# SH3-USB_AND_UART.net
KiCad netlist of a schematic drawn in Altium Designer
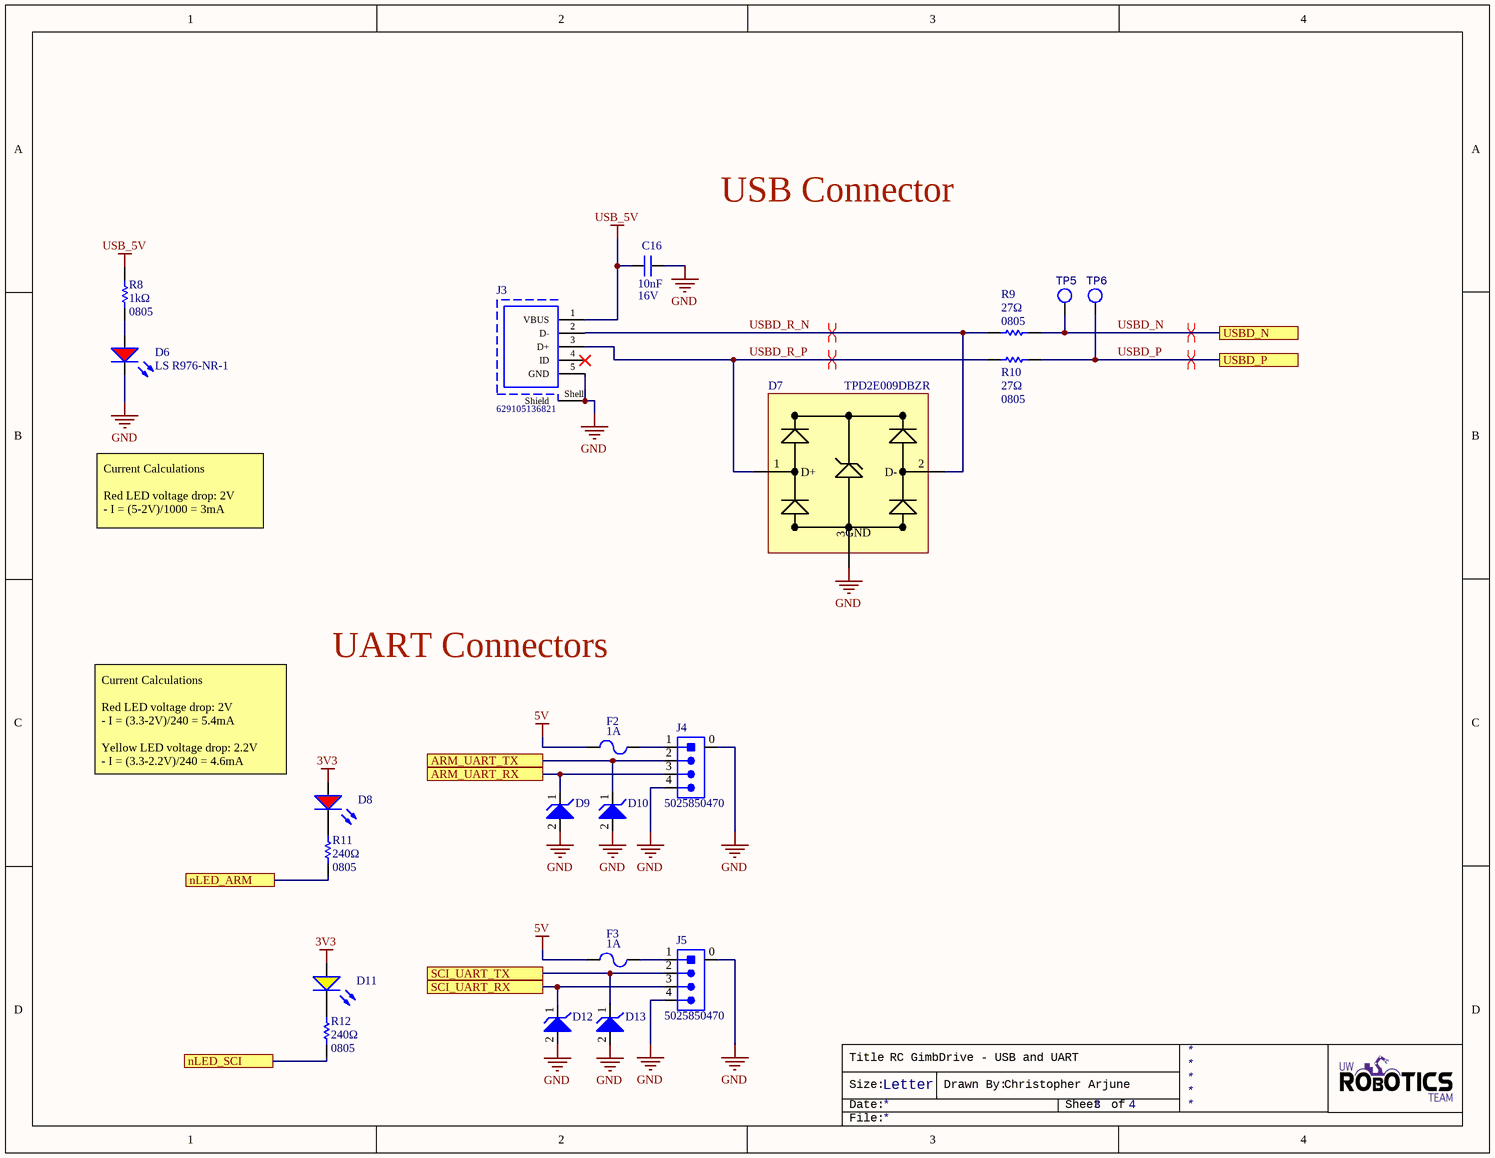
[diagram p0: SH3-USB AND UART.SchDoc]

(export (version "E")
  (design (tool "Eeschema 10.0.6"))
  (components
    (comp (ref "C16")
      (value "~")
      (footprint "CAPC2012X140N")
      (description "CAP CER 10000PF 16V X7R 0805")
      (fields
        (field (name "TOLERANCE") "10%")
        (field (name "CAPACITANCE") "10nF")
        (field (name "VOLTAGE RATING") "16V")
      )
      (libsource (lib "*") (part "CAP_10nF_16V_0805"))
    )
    (comp (ref "D6")
      (value "LS R976-NR-1")
      (footprint "LED_0805_LINE")
      (description "LED RED DIFFUSED 0805 SMD")
      (libsource (lib "UWRT_Schematic_Library_2020") (part "DIO_LED_R"))
    )
    (comp (ref "D7")
      (value "TVS_DIODE_USB_5.5V")
      (footprint "SOT23-3")
      (description "ESD Suppressor Diode Arrays 8KV 3-Pin SOT-23 T/R")
      (fields
        (field (name "MANUFACTURER") "Texas Instruments")
        (field (name "MANUFACTURER PART NUMBER") "TPD2E009DBZR")
      )
      (libsource (lib "UWRT_Schematic_Library_2020") (part "TVS_DIODE_USB_5.5V"))
    )
    (comp (ref "D8")
      (value "LS R976-NR-1")
      (footprint "LED_0805_RED")
      (description "LED RED DIFFUSED 0805 SMD")
      (libsource (lib "UWRT_Schematic_Library_2020") (part "DIO_LED_R"))
    )
    (comp (ref "D9")
      (value "TVS_DIODE_UNIDIR_3.3V")
      (footprint "SOD523")
      (description "TVS DIODE 3.3V 14.1V SOD523. Used to protect each connector input line going into the MCU.")
      (libsource (lib "UWRT_Schematic_Library_2020") (part "TVS_DIODE_UNIDIR_3.3V"))
    )
    (comp (ref "D10")
      (value "TVS_DIODE_UNIDIR_3.3V")
      (footprint "SOD523")
      (description "TVS DIODE 3.3V 14.1V SOD523. Used to protect each connector input line going into the MCU.")
      (libsource (lib "UWRT_Schematic_Library_2020") (part "TVS_DIODE_UNIDIR_3.3V"))
    )
    (comp (ref "D11")
      (value "LY R976-PS-36")
      (footprint "LED_0805_YELLOW")
      (description "LED YELLOW DIFFUSED 0805 SMD")
      (libsource (lib "UWRT_Schematic_Library_2020") (part "DIO_LED_Y"))
    )
    (comp (ref "D12")
      (value "TVS_DIODE_UNIDIR_3.3V")
      (footprint "SOD523")
      (description "TVS DIODE 3.3V 14.1V SOD523. Used to protect each connector input line going into the MCU.")
      (libsource (lib "UWRT_Schematic_Library_2020") (part "TVS_DIODE_UNIDIR_3.3V"))
    )
    (comp (ref "D13")
      (value "TVS_DIODE_UNIDIR_3.3V")
      (footprint "SOD523")
      (description "TVS DIODE 3.3V 14.1V SOD523. Used to protect each connector input line going into the MCU.")
      (libsource (lib "UWRT_Schematic_Library_2020") (part "TVS_DIODE_UNIDIR_3.3V"))
    )
    (comp (ref "F2")
      (value "FUSE_1A_1206")
      (footprint "FUSC3215X78N")
      (description "FUSE BOARD MOUNT 1A 125VAC 63VDC")
      (fields (field (name "CURRENT RATING") "1A"))
      (libsource (lib "UWRT_Schematic_Library_2020") (part "FUSE_1A_1206"))
    )
    (comp (ref "F3")
      (value "FUSE_1A_1206")
      (footprint "FUSC3215X78N")
      (description "FUSE BOARD MOUNT 1A 125VAC 63VDC")
      (fields (field (name "CURRENT RATING") "1A"))
      (libsource (lib "UWRT_Schematic_Library_2020") (part "FUSE_1A_1206"))
    )
    (comp (ref "J3")
      (value "629105136821")
      (footprint "629105136821")
      (description "Micro USB 2.0 Type B Receptacle WR-COM, Horizontal, SMT, with Pads and Pegs")
      (fields (field (name "MANUFACTURER") "Wurth Elektronik") (field (name "PUBLISHER") "WurthElektronik"))
      (libsource (lib "Altium Content Vault") (part "WE-USB-5-1SHLD"))
    )
    (comp (ref "J4")
      (value "CON_4M_SM_RA")
      (footprint "MOLEX-5025850470")
      (description "CONN HEADER SMD RIGHT ANGLE 1.5 MM PITCH")
      (fields (field (name "MANUFACTURER") "Molex") (field (name "MANUFACTOR NUMBER") "5025850470"))
      (libsource (lib "UWRT_Schematic_Library_2020") (part "CON_4M_SM_RA"))
    )
    (comp (ref "J5")
      (value "CON_4M_SM_RA")
      (footprint "MOLEX-5025850470")
      (description "CONN HEADER SMD RIGHT ANGLE 1.5 MM PITCH")
      (fields (field (name "MANUFACTURER") "Molex") (field (name "MANUFACTOR NUMBER") "5025850470"))
      (libsource (lib "UWRT_Schematic_Library_2020") (part "CON_4M_SM_RA"))
    )
    (comp (ref "R8")
      (value "1kΩ")
      (footprint "RESC2012X60N")
      (description "RES SMD 1K OHM 1% 1/8W 0805")
      (fields (field (name "TOLERANCE") "1%") (field (name "CASE CODE (IMPERIAL)") "0805"))
      (libsource (lib "UWRT_Schematic_Library_2020") (part "RES_1kΩ_0805"))
    )
    (comp (ref "R9")
      (value "RES_27Ω_0805")
      (footprint "RESC2012X60N")
      (description "RES 27 OHM 1% 1/8W 0805")
      (fields
        (field (name "TOLERANCE") "1%")
        (field (name "RESISTANCE") "27Ω")
        (field (name "CASE/PACKAGE") "0805")
      )
      (libsource (lib "UWRT_Schematic_Library_2020") (part "RES_27Ω_0805_1%"))
    )
    (comp (ref "R10")
      (value "RES_27Ω_0805")
      (footprint "RESC2012X60N")
      (description "RES 27 OHM 1% 1/8W 0805")
      (fields
        (field (name "TOLERANCE") "1%")
        (field (name "RESISTANCE") "27Ω")
        (field (name "CASE/PACKAGE") "0805")
      )
      (libsource (lib "UWRT_Schematic_Library_2020") (part "RES_27Ω_0805_1%"))
    )
    (comp (ref "R11")
      (value "240")
      (footprint "RESC2012X60N")
      (description "RES 240 OHM 1% 1/8W 0805")
      (fields
        (field (name "TOLERANCE") "1%")
        (field (name "RESISTANCE") "240Ω")
        (field (name "CASE CODE (IMPERIAL)") "0805")
      )
      (libsource (lib "UWRT_Schematic_Library_2020") (part "RES_240Ω_0805_1%"))
    )
    (comp (ref "R12")
      (value "240")
      (footprint "RESC2012X60N")
      (description "RES 240 OHM 1% 1/8W 0805")
      (fields
        (field (name "TOLERANCE") "1%")
        (field (name "RESISTANCE") "240Ω")
        (field (name "CASE CODE (IMPERIAL)") "0805")
      )
      (libsource (lib "UWRT_Schematic_Library_2020") (part "RES_240Ω_0805_1%"))
    )
    (comp (ref "TP5")
      (value "TESTPOINT_LOOP")
      (footprint "TESTPOINT_LOOP")
      (description "Loop testpoint through-hole pad")
      (libsource (lib "UWRT_Schematic_Library_2020") (part "TESTPOINT_LOOP"))
    )
    (comp (ref "TP6")
      (value "TESTPOINT_LOOP")
      (footprint "TESTPOINT_LOOP")
      (description "Loop testpoint through-hole pad")
      (libsource (lib "UWRT_Schematic_Library_2020") (part "TESTPOINT_LOOP"))
    )
  )
  (nets
    (net (code "1") (name "/ARM_UART_RX") (class "Default")
      (node (ref "D9") (pin "1") (pinfunction "1_1") (pintype "passive"))
      (node (ref "J4") (pin "3") (pinfunction "3_3") (pintype "passive"))
    )
    (net (code "2") (name "/ARM_UART_TX") (class "Default")
      (node (ref "D10") (pin "1") (pinfunction "1_1") (pintype "passive"))
      (node (ref "J4") (pin "2") (pinfunction "2_2") (pintype "passive"))
    )
    (net (code "3") (name "/SCI_UART_RX") (class "Default")
      (node (ref "D12") (pin "1") (pinfunction "1_1") (pintype "passive"))
      (node (ref "J5") (pin "3") (pinfunction "3_3") (pintype "passive"))
    )
    (net (code "4") (name "/SCI_UART_TX") (class "Default")
      (node (ref "D13") (pin "1") (pinfunction "1_1") (pintype "passive"))
      (node (ref "J5") (pin "2") (pinfunction "2_2") (pintype "passive"))
    )
    (net (code "5") (name "/USBD_N") (class "Default")
      (node (ref "R9") (pin "2") (pinfunction "2_2") (pintype "passive"))
      (node (ref "TP5") (pin "1") (pintype "passive"))
    )
    (net (code "6") (name "/USBD_P") (class "Default")
      (node (ref "R10") (pin "2") (pinfunction "2_2") (pintype "passive"))
      (node (ref "TP6") (pin "1") (pintype "passive"))
    )
    (net (code "7") (name "/USBD_R_N") (class "Default")
      (node (ref "D7") (pin "2") (pinfunction "D-_2") (pintype "passive"))
      (node (ref "J3") (pin "2") (pinfunction "D-_2") (pintype "passive"))
      (node (ref "R9") (pin "1") (pinfunction "1_1") (pintype "passive"))
    )
    (net (code "8") (name "/USBD_R_P") (class "Default")
      (node (ref "D7") (pin "1") (pinfunction "D+_1") (pintype "passive"))
      (node (ref "J3") (pin "3") (pinfunction "D+_3") (pintype "passive"))
      (node (ref "R10") (pin "1") (pinfunction "1_1") (pintype "passive"))
    )
    (net (code "9") (name "/nLED_ARM") (class "Default")
      (node (ref "R11") (pin "1") (pinfunction "1_1") (pintype "passive"))
    )
    (net (code "10") (name "/nLED_SCI") (class "Default")
      (node (ref "R12") (pin "1") (pinfunction "1_1") (pintype "passive"))
    )
    (net (code "11") (name "3V3") (class "Default")
      (node (ref "D11") (pin "1") (pinfunction "A_1") (pintype "passive"))
      (node (ref "D8") (pin "1") (pinfunction "A_1") (pintype "passive"))
    )
    (net (code "12") (name "5V") (class "Default")
      (node (ref "F2") (pin "1") (pinfunction "1_1") (pintype "passive"))
      (node (ref "F3") (pin "1") (pinfunction "1_1") (pintype "passive"))
    )
    (net (code "13") (name "GND") (class "Default")
      (node (ref "C16") (pin "2") (pinfunction "2_2") (pintype "passive"))
      (node (ref "D10") (pin "2") (pinfunction "2_2") (pintype "passive"))
      (node (ref "D12") (pin "2") (pinfunction "2_2") (pintype "passive"))
      (node (ref "D13") (pin "2") (pinfunction "2_2") (pintype "passive"))
      (node (ref "D6") (pin "2") (pinfunction "K_2") (pintype "passive"))
      (node (ref "D7") (pin "3") (pinfunction "GND_3") (pintype "passive"))
      (node (ref "D9") (pin "2") (pinfunction "2_2") (pintype "passive"))
      (node (ref "J3") (pin "5") (pinfunction "GND_5") (pintype "passive"))
      (node (ref "J3") (pin "Shell") (pinfunction "Shield_Shell") (pintype "passive"))
      (node (ref "J4") (pin "0") (pinfunction "0_0") (pintype "passive"))
      (node (ref "J4") (pin "4") (pinfunction "4_4") (pintype "passive"))
      (node (ref "J5") (pin "0") (pinfunction "0_0") (pintype "passive"))
      (node (ref "J5") (pin "4") (pinfunction "4_4") (pintype "passive"))
    )
    (net (code "14") (name "Net-(D6-A)") (class "Default")
      (node (ref "D6") (pin "1") (pinfunction "A_1") (pintype "passive"))
      (node (ref "R8") (pin "1") (pinfunction "1_1") (pintype "passive"))
    )
    (net (code "15") (name "Net-(D8-K)") (class "Default")
      (node (ref "D8") (pin "2") (pinfunction "K_2") (pintype "passive"))
      (node (ref "R11") (pin "2") (pinfunction "2_2") (pintype "passive"))
    )
    (net (code "16") (name "Net-(D11-K)") (class "Default")
      (node (ref "D11") (pin "2") (pinfunction "K_2") (pintype "passive"))
      (node (ref "R12") (pin "2") (pinfunction "2_2") (pintype "passive"))
    )
    (net (code "17") (name "Net-(F2-Pad2)") (class "Default")
      (node (ref "F2") (pin "2") (pinfunction "2_2") (pintype "passive"))
      (node (ref "J4") (pin "1") (pinfunction "1_1") (pintype "passive"))
    )
    (net (code "18") (name "Net-(F3-Pad2)") (class "Default")
      (node (ref "F3") (pin "2") (pinfunction "2_2") (pintype "passive"))
      (node (ref "J5") (pin "1") (pinfunction "1_1") (pintype "passive"))
    )
    (net (code "19") (name "USB_5V") (class "Default")
      (node (ref "C16") (pin "1") (pinfunction "1_1") (pintype "passive"))
      (node (ref "J3") (pin "1") (pinfunction "VBUS_1") (pintype "passive"))
      (node (ref "R8") (pin "2") (pinfunction "2_2") (pintype "passive"))
    )
    (net (code "20") (name "unconnected-(J3-ID-Pad4)") (class "Default")
      (node (ref "J3") (pin "4") (pinfunction "ID_4") (pintype "passive+no_connect"))
    )
  )
)
